# ltk-mw-rx.net
KiCad netlist of a schematic drawn in Altium Designer
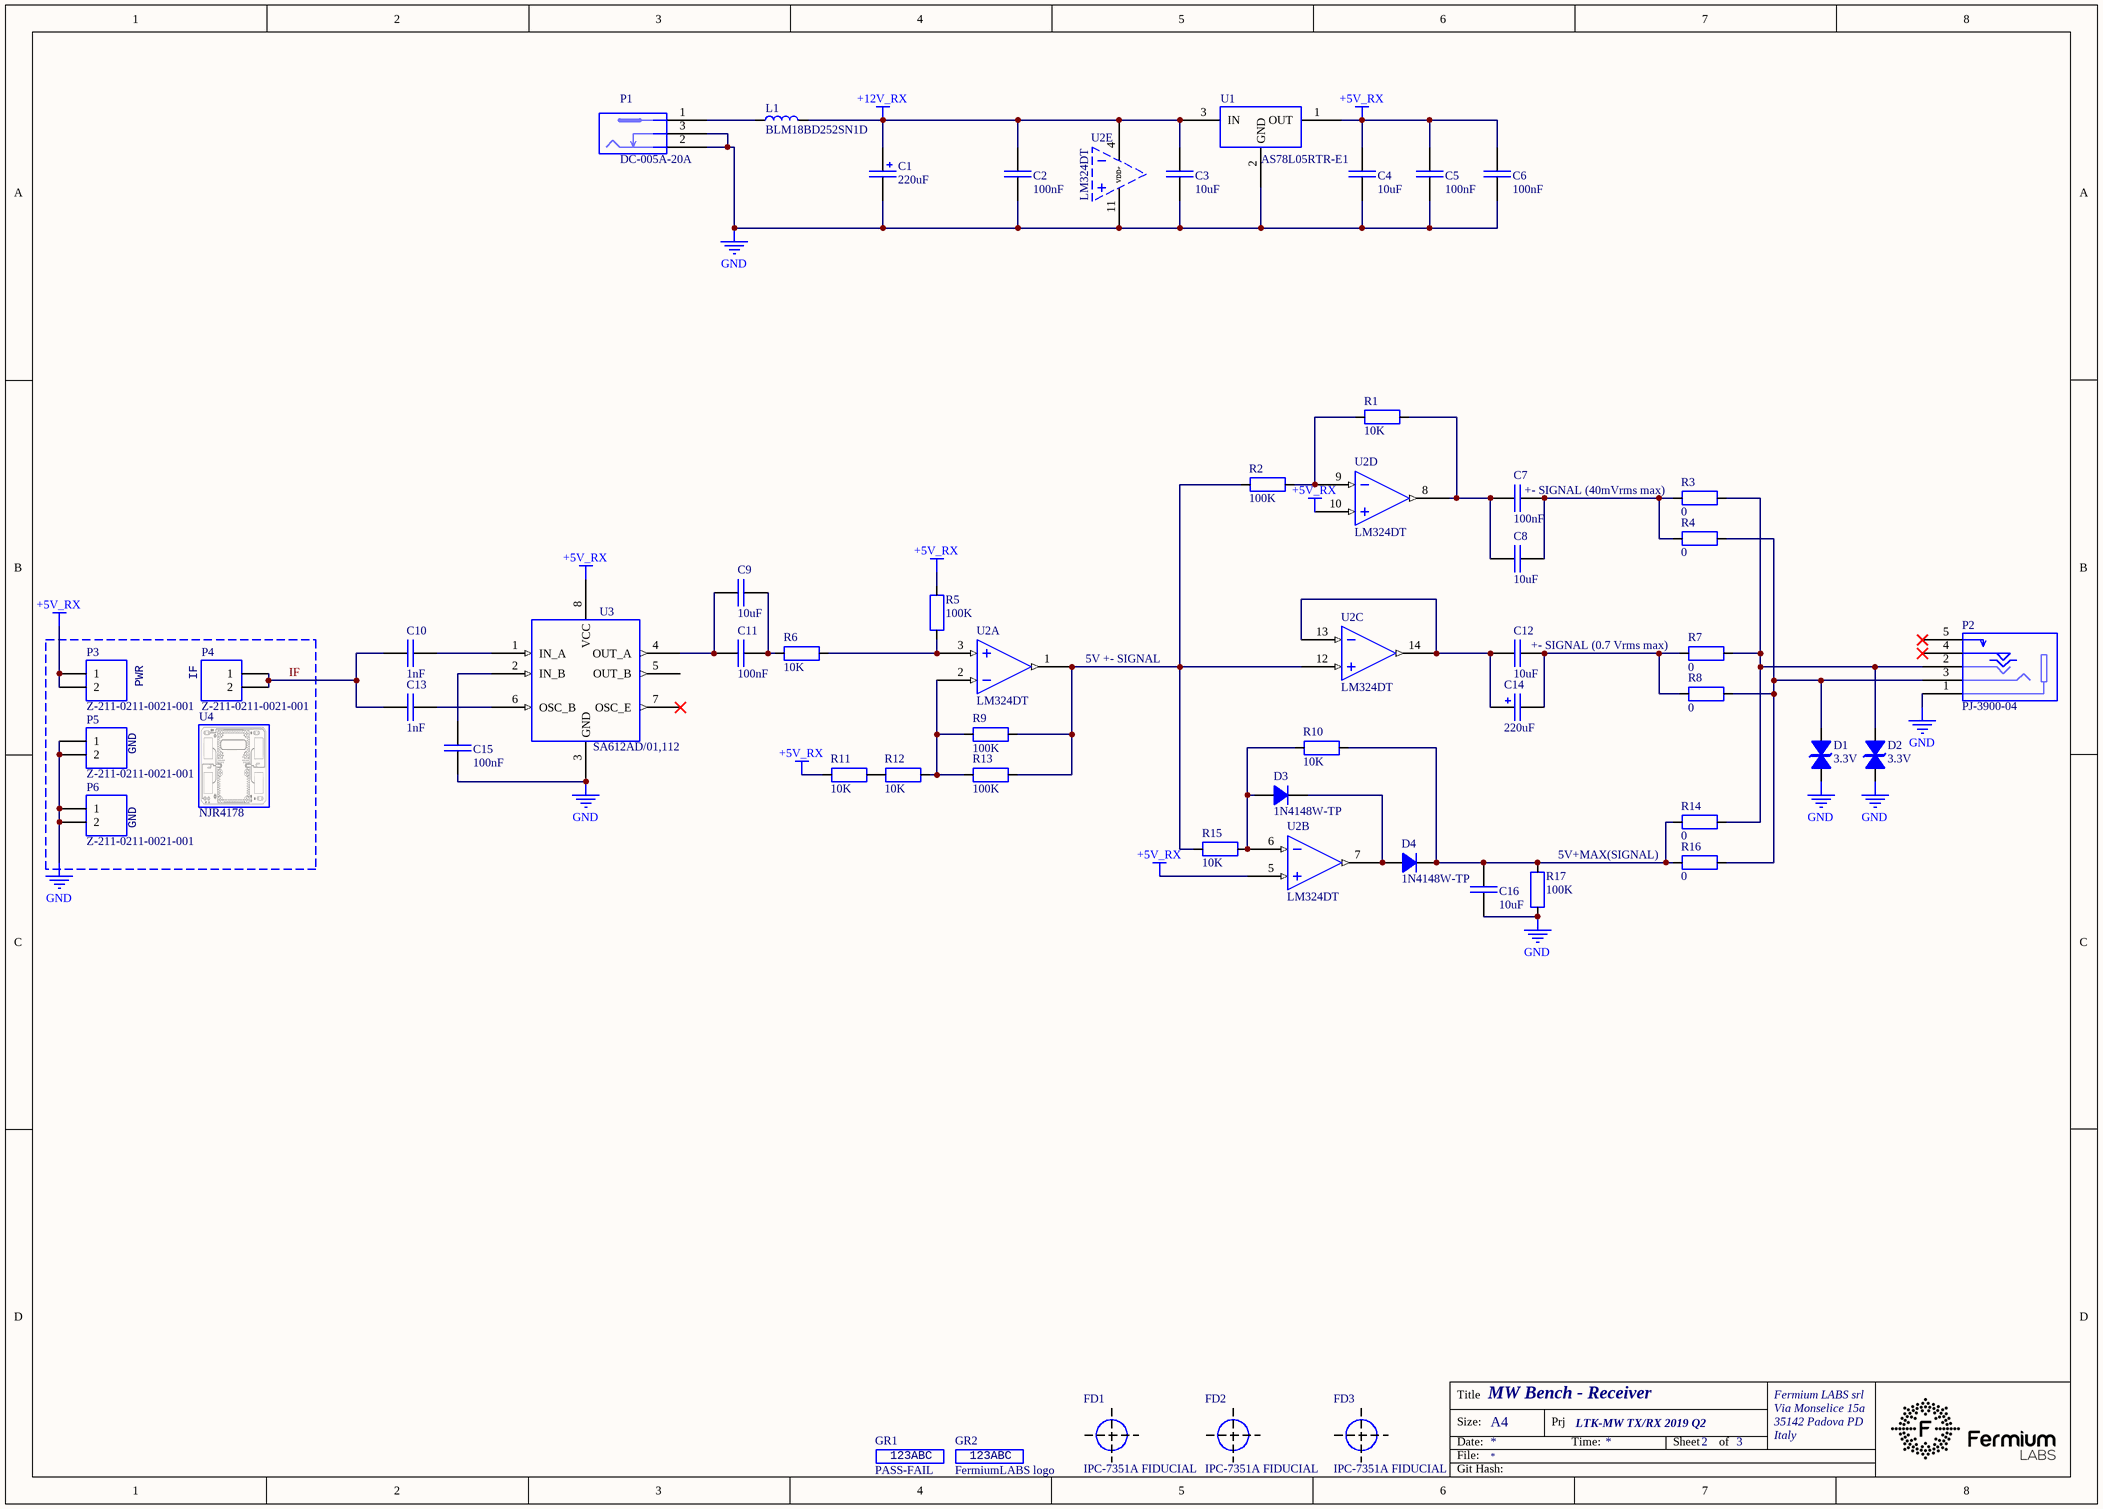
[diagram p0: ltk-mw-rx.SchDoc]

(export (version "E")
  (design (tool "Eeschema 10.0.6"))
  (components
    (comp (ref "C1")
      (value "220uF")
      (footprint "3924B366-8672-45E9-B0BE-62DACC24E783")
      (description "CAP  THT ELEC 220uF 25V 20%")
      (fields (field (name "PART NUMBER") "1a28df19-6d3e-4a71-836c-f22920f8e8ab"))
      (libsource (lib "frmdblib") (part "GENERIC_C_ELEC"))
    )
    (comp (ref "C2")
      (value "100nF")
      (footprint "CAP 0603_1608")
      (description "CAP SMD MLCC 100nF 25V 0603 X7R")
      (fields (field (name "PART NUMBER") "02841f84-ac15-41b5-9e17-915f8f067828"))
      (libsource (lib "frmdblib") (part "GENERIC_C"))
    )
    (comp (ref "C3")
      (value "10uF")
      (footprint "CAP 0805_2012")
      (description "CAP SMD MLCC 10uF 25V 0805 X5R")
      (fields (field (name "PART NUMBER") "1ffbe5a9-0884-4740-bdad-20a6a98400e6"))
      (libsource (lib "frmdblib") (part "GENERIC_C"))
    )
    (comp (ref "C4")
      (value "10uF")
      (footprint "CAP 0805_2012")
      (description "CAP SMD MLCC 10uF 25V 0805 X5R")
      (fields (field (name "PART NUMBER") "1ffbe5a9-0884-4740-bdad-20a6a98400e6"))
      (libsource (lib "frmdblib") (part "GENERIC_C"))
    )
    (comp (ref "C5")
      (value "100nF")
      (footprint "CAP 0603_1608")
      (description "CAP SMD MLCC 100nF 25V 0603 X7R")
      (fields (field (name "PART NUMBER") "02841f84-ac15-41b5-9e17-915f8f067828"))
      (libsource (lib "frmdblib") (part "GENERIC_C"))
    )
    (comp (ref "C6")
      (value "100nF")
      (footprint "CAP 0603_1608")
      (description "CAP SMD MLCC 100nF 25V 0603 X7R")
      (fields (field (name "PART NUMBER") "02841f84-ac15-41b5-9e17-915f8f067828"))
      (libsource (lib "frmdblib") (part "GENERIC_C"))
    )
    (comp (ref "C7")
      (value "100nF")
      (footprint "CAP 0603_1608")
      (description "CAP SMD MLCC 100nF 25V 0603 X7R")
      (fields (field (name "PART NUMBER") "02841f84-ac15-41b5-9e17-915f8f067828"))
      (libsource (lib "frmdblib") (part "GENERIC_C"))
    )
    (comp (ref "C8")
      (value "10uF")
      (footprint "CAP 0805_2012")
      (description "CAP SMD MLCC 10uF 25V 0805 X5R")
      (fields (field (name "PART NUMBER") "1ffbe5a9-0884-4740-bdad-20a6a98400e6"))
      (libsource (lib "frmdblib") (part "GENERIC_C"))
    )
    (comp (ref "C9")
      (value "10uF")
      (footprint "CAP 0805_2012")
      (description "CAP SMD MLCC 10uF 25V 0805 X5R")
      (fields (field (name "PART NUMBER") "1ffbe5a9-0884-4740-bdad-20a6a98400e6"))
      (libsource (lib "frmdblib") (part "GENERIC_C"))
    )
    (comp (ref "C10")
      (value "1nF")
      (footprint "CAP 0603_1608")
      (description "CAP SMD MLCC 1nF 50V 0603 X7R")
      (fields (field (name "PART NUMBER") "0eca2548-3630-4fea-a3d5-94248c1cae74"))
      (libsource (lib "frmdblib") (part "GENERIC_C"))
    )
    (comp (ref "C11")
      (value "100nF")
      (footprint "CAP 0603_1608")
      (description "CAP SMD MLCC 100nF 25V 0603 X7R")
      (fields (field (name "PART NUMBER") "02841f84-ac15-41b5-9e17-915f8f067828"))
      (libsource (lib "frmdblib") (part "GENERIC_C"))
    )
    (comp (ref "C12")
      (value "10uF")
      (footprint "CAP 0805_2012")
      (description "CAP SMD MLCC 10uF 25V 0805 X5R")
      (fields (field (name "PART NUMBER") "1ffbe5a9-0884-4740-bdad-20a6a98400e6"))
      (libsource (lib "frmdblib") (part "GENERIC_C"))
    )
    (comp (ref "C13")
      (value "1nF")
      (footprint "CAP 0603_1608")
      (description "CAP SMD MLCC 1nF 50V 0603 X7R")
      (fields (field (name "PART NUMBER") "0eca2548-3630-4fea-a3d5-94248c1cae74"))
      (libsource (lib "frmdblib") (part "GENERIC_C"))
    )
    (comp (ref "C14")
      (value "220uF")
      (footprint "3924B366-8672-45E9-B0BE-62DACC24E783")
      (description "CAP  THT ELEC 220uF 25V 20%")
      (fields (field (name "PART NUMBER") "1a28df19-6d3e-4a71-836c-f22920f8e8ab"))
      (libsource (lib "frmdblib") (part "GENERIC_C_ELEC"))
    )
    (comp (ref "C15")
      (value "100nF")
      (footprint "CAP 0603_1608")
      (description "CAP SMD MLCC 100nF 25V 0603 X7R")
      (fields (field (name "PART NUMBER") "02841f84-ac15-41b5-9e17-915f8f067828"))
      (libsource (lib "frmdblib") (part "GENERIC_C"))
    )
    (comp (ref "C16")
      (value "10uF")
      (footprint "CAP 0805_2012")
      (description "CAP SMD MLCC 10uF 25V 0805 X5R")
      (fields (field (name "PART NUMBER") "1ffbe5a9-0884-4740-bdad-20a6a98400e6"))
      (libsource (lib "frmdblib") (part "GENERIC_C"))
    )
    (comp (ref "D1")
      (value "3.3V")
      (footprint "SOD523F")
      (description "DIODE SMD TVS 3.3V BIDIRECTIONAL SOD-523")
      (fields (field (name "PART NUMBER") "d6266fd0-7428-4fb9-a062-338cdce926fd"))
      (libsource (lib "frmdblib") (part "GENERIC_D_TVS_BI"))
    )
    (comp (ref "D2")
      (value "3.3V")
      (footprint "SOD523F")
      (description "DIODE SMD TVS 3.3V BIDIRECTIONAL SOD-523")
      (fields (field (name "PART NUMBER") "d6266fd0-7428-4fb9-a062-338cdce926fd"))
      (libsource (lib "frmdblib") (part "GENERIC_D_TVS_BI"))
    )
    (comp (ref "D3")
      (value "1N4148W-TP")
      (footprint "SOD-123")
      (description "DIODE SMD 100V 150mA 1.5Vf SOD-123 4148")
      (fields (field (name "PART NUMBER") "5e920700-75df-48e3-84dd-8f9f777caed8"))
      (libsource (lib "frmdblib") (part "GENERIC_D"))
    )
    (comp (ref "D4")
      (value "1N4148W-TP")
      (footprint "SOD-123")
      (description "DIODE SMD 100V 150mA 1.5Vf SOD-123 4148")
      (fields (field (name "PART NUMBER") "5e920700-75df-48e3-84dd-8f9f777caed8"))
      (libsource (lib "frmdblib") (part "GENERIC_D"))
    )
    (comp (ref "FD1")
      (value "IPC-7351A FIDUCIAL")
      (footprint "FIDUCIAL-IPC-7351A")
      (description "GRAPHICS FIDUCIAL IPC-7351A")
      (fields (field (name "PART NUMBER") "19da4612-eb95-43bb-9984-553a52b2a224"))
      (libsource (lib "frmdblib") (part "GENERIC_FIDUCIAL"))
    )
    (comp (ref "FD2")
      (value "IPC-7351A FIDUCIAL")
      (footprint "FIDUCIAL-IPC-7351A")
      (description "GRAPHICS FIDUCIAL IPC-7351A")
      (fields (field (name "PART NUMBER") "19da4612-eb95-43bb-9984-553a52b2a224"))
      (libsource (lib "frmdblib") (part "GENERIC_FIDUCIAL"))
    )
    (comp (ref "FD3")
      (value "IPC-7351A FIDUCIAL")
      (footprint "FIDUCIAL-IPC-7351A")
      (description "GRAPHICS FIDUCIAL IPC-7351A")
      (fields (field (name "PART NUMBER") "19da4612-eb95-43bb-9984-553a52b2a224"))
      (libsource (lib "frmdblib") (part "GENERIC_FIDUCIAL"))
    )
    (comp (ref "GR1")
      (value "PASS-FAIL")
      (footprint "0B1556B7-A534-4801-B57D-01EFA34B1205")
      (description "GRAPHICS PASS-FAIL MARK")
      (fields (field (name "PART NUMBER") "d1abe19f-3fed-4f20-b2ed-afc0ffbc6628"))
      (libsource (lib "frmdblib") (part "GENERIC_GRAPHIC"))
    )
    (comp (ref "GR2")
      (value "FermiumLABS logo")
      (footprint "5394DE47-A0E8-4329-8464-7791B7C19310")
      (description "GRAPHICS LOGO FERMIUM LABS SRL")
      (fields (field (name "PART NUMBER") "50f8ea88-0034-49fe-a263-d8e97bc35e2f"))
      (libsource (lib "frmdblib") (part "GENERIC_GRAPHIC"))
    )
    (comp (ref "L1")
      (value "BLM18BD252SN1D")
      (footprint "FER 0603_1608")
      (description "FER SMD CHIP 0603 400mA 1k@100MHz 500mOhm")
      (fields (field (name "PART NUMBER") "c9e30ae8-9d5b-4135-a079-b1147da846d8"))
      (libsource (lib "frmdblib") (part "GENERIC_L"))
    )
    (comp (ref "P1")
      (value "DC-005A-20A")
      (footprint "F0972D8A-C5C0-4A84-836D-A9666EE65C2D")
      (description "CONN THT DC JACK 0.5A 30VDC 5Kcycles")
      (fields (field (name "PART NUMBER") "b53db51a-1725-412b-9039-fa7a45c7c438"))
      (libsource (lib "frmdblib") (part "34A1CD0B-E262-46EF-B9F1-39CB809C308F"))
    )
    (comp (ref "P2")
      (value "PJ-3900-04")
      (footprint "7EF2B92C-0FC9-4C85-B662-5CEC65BFCCC4")
      (description "CONN THT 3.5mm AUDIO STEREO AUX SWITCH")
      (fields (field (name "PART NUMBER") "80507a24-5d7c-4cf5-953e-f54832d54564"))
      (libsource (lib "frmdblib") (part "46E41D2F-79BD-46AC-B778-70B2D50A946A"))
    )
    (comp (ref "P3")
      (value "Z-211-0211-0021-001")
      (footprint "0FBEB40D-2B6D-43C7-945F-A2D40A82B953")
      (description "CONN THT PIN HEADER 2P MALE 2.54mm")
      (fields (field (name "PART NUMBER") "fb9043ef-1dd5-4a9c-8c1a-da0c667690ac"))
      (libsource (lib "frmdblib") (part "Header 2"))
    )
    (comp (ref "P4")
      (value "Z-211-0211-0021-001")
      (footprint "0FBEB40D-2B6D-43C7-945F-A2D40A82B953")
      (description "CONN THT PIN HEADER 2P MALE 2.54mm")
      (fields (field (name "PART NUMBER") "fb9043ef-1dd5-4a9c-8c1a-da0c667690ac"))
      (libsource (lib "") (part "Header 2_1"))
    )
    (comp (ref "P5")
      (value "Z-211-0211-0021-001")
      (footprint "0FBEB40D-2B6D-43C7-945F-A2D40A82B953")
      (description "CONN THT PIN HEADER 2P MALE 2.54mm")
      (fields (field (name "PART NUMBER") "fb9043ef-1dd5-4a9c-8c1a-da0c667690ac"))
      (libsource (lib "frmdblib") (part "Header 2"))
    )
    (comp (ref "P6")
      (value "Z-211-0211-0021-001")
      (footprint "0FBEB40D-2B6D-43C7-945F-A2D40A82B953")
      (description "CONN THT PIN HEADER 2P MALE 2.54mm")
      (fields (field (name "PART NUMBER") "fb9043ef-1dd5-4a9c-8c1a-da0c667690ac"))
      (libsource (lib "frmdblib") (part "Header 2"))
    )
    (comp (ref "R1")
      (value "10K")
      (footprint "RES 0603_1608")
      (description "RES SMD 10K OHM 1% 1/10W 0603")
      (fields (field (name "PART NUMBER") "93242766-ba1d-462d-b58f-ce1dfc4129c8"))
      (libsource (lib "frmdblib") (part "GENERIC_R"))
    )
    (comp (ref "R2")
      (value "100K")
      (footprint "RES 0603_1608")
      (description "RES SMD 100K OHM 1% 1/10W 0603")
      (fields (field (name "PART NUMBER") "76af10b3-9d85-4b5c-a2d6-26cc74f432f7"))
      (libsource (lib "frmdblib") (part "GENERIC_R"))
    )
    (comp (ref "R3")
      (value "0")
      (footprint "RES 0603_1608")
      (description "RES SMD 0 OHM 5% 1/10W 0603")
      (fields (field (name "PART NUMBER") "6ae227f9-847f-4766-8522-e11a83531204"))
      (libsource (lib "frmdblib") (part "GENERIC_R"))
    )
    (comp (ref "R4")
      (value "0")
      (footprint "RES 0603_1608")
      (description "RES SMD 0 OHM 5% 1/10W 0603")
      (fields (field (name "PART NUMBER") "6ae227f9-847f-4766-8522-e11a83531204"))
      (libsource (lib "frmdblib") (part "GENERIC_R"))
    )
    (comp (ref "R5")
      (value "100K")
      (footprint "RES 0603_1608")
      (description "RES SMD 100K OHM 1% 1/10W 0603")
      (fields (field (name "PART NUMBER") "76af10b3-9d85-4b5c-a2d6-26cc74f432f7"))
      (libsource (lib "frmdblib") (part "GENERIC_R"))
    )
    (comp (ref "R6")
      (value "10K")
      (footprint "RES 0603_1608")
      (description "RES SMD 10K OHM 1% 1/10W 0603")
      (fields (field (name "PART NUMBER") "93242766-ba1d-462d-b58f-ce1dfc4129c8"))
      (libsource (lib "frmdblib") (part "GENERIC_R"))
    )
    (comp (ref "R7")
      (value "0")
      (footprint "RES 0603_1608")
      (description "RES SMD 0 OHM 5% 1/10W 0603")
      (fields (field (name "PART NUMBER") "6ae227f9-847f-4766-8522-e11a83531204"))
      (libsource (lib "frmdblib") (part "GENERIC_R"))
    )
    (comp (ref "R8")
      (value "0")
      (footprint "RES 0603_1608")
      (description "RES SMD 0 OHM 5% 1/10W 0603")
      (fields (field (name "PART NUMBER") "6ae227f9-847f-4766-8522-e11a83531204"))
      (libsource (lib "frmdblib") (part "GENERIC_R"))
    )
    (comp (ref "R9")
      (value "100K")
      (footprint "RES 0603_1608")
      (description "RES SMD 100K OHM 1% 1/10W 0603")
      (fields (field (name "PART NUMBER") "76af10b3-9d85-4b5c-a2d6-26cc74f432f7"))
      (libsource (lib "frmdblib") (part "GENERIC_R"))
    )
    (comp (ref "R10")
      (value "10K")
      (footprint "RES 0603_1608")
      (description "RES SMD 10K OHM 1% 1/10W 0603")
      (fields (field (name "PART NUMBER") "93242766-ba1d-462d-b58f-ce1dfc4129c8"))
      (libsource (lib "frmdblib") (part "GENERIC_R"))
    )
    (comp (ref "R11")
      (value "10K")
      (footprint "RES 0603_1608")
      (description "RES SMD 10K OHM 1% 1/10W 0603")
      (fields (field (name "PART NUMBER") "93242766-ba1d-462d-b58f-ce1dfc4129c8"))
      (libsource (lib "frmdblib") (part "GENERIC_R"))
    )
    (comp (ref "R12")
      (value "10K")
      (footprint "RES 0603_1608")
      (description "RES SMD 10K OHM 1% 1/10W 0603")
      (fields (field (name "PART NUMBER") "93242766-ba1d-462d-b58f-ce1dfc4129c8"))
      (libsource (lib "frmdblib") (part "GENERIC_R"))
    )
    (comp (ref "R13")
      (value "100K")
      (footprint "RES 0603_1608")
      (description "RES SMD 100K OHM 1% 1/10W 0603")
      (fields (field (name "PART NUMBER") "76af10b3-9d85-4b5c-a2d6-26cc74f432f7"))
      (libsource (lib "frmdblib") (part "GENERIC_R"))
    )
    (comp (ref "R14")
      (value "0")
      (footprint "RES 0603_1608")
      (description "RES SMD 0 OHM 5% 1/10W 0603")
      (fields (field (name "PART NUMBER") "6ae227f9-847f-4766-8522-e11a83531204"))
      (libsource (lib "frmdblib") (part "GENERIC_R"))
    )
    (comp (ref "R15")
      (value "10K")
      (footprint "RES 0603_1608")
      (description "RES SMD 10K OHM 1% 1/10W 0603")
      (fields (field (name "PART NUMBER") "93242766-ba1d-462d-b58f-ce1dfc4129c8"))
      (libsource (lib "frmdblib") (part "GENERIC_R"))
    )
    (comp (ref "R16")
      (value "0")
      (footprint "RES 0603_1608")
      (description "RES SMD 0 OHM 5% 1/10W 0603")
      (fields (field (name "PART NUMBER") "6ae227f9-847f-4766-8522-e11a83531204"))
      (libsource (lib "frmdblib") (part "GENERIC_R"))
    )
    (comp (ref "R17")
      (value "100K")
      (footprint "RES 0603_1608")
      (description "RES SMD 100K OHM 1% 1/10W 0603")
      (fields (field (name "PART NUMBER") "76af10b3-9d85-4b5c-a2d6-26cc74f432f7"))
      (libsource (lib "frmdblib") (part "GENERIC_R"))
    )
    (comp (ref "U1")
      (value "AS78L05RTR-E1")
      (footprint "E733EFB9-FE91-4AE9-9197-29251971C3DC")
      (description "IC SMD LINEAR VOLTAGE REGULATOR 5V 100mA SOT-89")
      (fields (field (name "PART NUMBER") "fd64863e-487f-4688-b264-696c0ba5456b"))
      (libsource (lib "frmdblib") (part "FCB39772-D6AF-4D61-BC58-A46A50428B6B"))
    )
    (comp (ref "U2")
      (value "LM324DT")
      (footprint "34355DA5-B1DA-47C2-A88A-ECF82120A4F7")
      (description "IC SMD OPAMP LM324DT SO-14")
      (fields (field (name "PART NUMBER") "21a85167-c328-42f7-a52e-365842c6dad3"))
      (libsource (lib "frmdblib") (part "B8DB4B19-8E9C-4F46-A390-7A352E041443"))
    )
    (comp (ref "U3")
      (value "SA612AD/01,112")
      (footprint "TI SOIC-8 D")
      (description "IC SMD RF MIXER SA612A SOIC-8")
      (fields (field (name "PART NUMBER") "a9622f6c-68f2-4f08-abc9-76f38977fdd3"))
      (libsource (lib "frmdblib") (part "A45114BD-821B-4F2C-91DA-34880533DC1E"))
    )
    (comp (ref "U4")
      (value "NJR4178")
      (footprint "25B19271-CD6F-4BC8-A99B-F617D566DC9C")
      (description "MODULE THT RADAR DOPPLER 10.525GHz NJR4178")
      (fields (field (name "PART NUMBER") "f0e19a38-18de-4253-8da2-aebb0c4083bd"))
      (libsource (lib "frmdblib") (part "687D5558-C857-4646-9F75-B643D2B4D9DF"))
    )
  )
  (nets
    (net (code "1") (name "+5V_RX") (class "Default")
      (node (ref "C4") (pin "2") (pintype "passive"))
      (node (ref "C5") (pin "2") (pintype "passive"))
      (node (ref "C6") (pin "2") (pintype "passive"))
      (node (ref "P3") (pin "1") (pinfunction "1_1") (pintype "passive"))
      (node (ref "P3") (pin "2") (pinfunction "2_2") (pintype "passive"))
      (node (ref "R11") (pin "2") (pintype "passive"))
      (node (ref "R5") (pin "1") (pintype "passive"))
      (node (ref "U1") (pin "1") (pinfunction "OUT_1") (pintype "passive"))
      (node (ref "U2") (pin "10") (pinfunction "IN+_10") (pintype "input"))
      (node (ref "U2") (pin "5") (pinfunction "IN+_5") (pintype "input"))
      (node (ref "U3") (pin "8") (pinfunction "VCC_8") (pintype "power_in"))
    )
    (net (code "2") (name "+12V_RX") (class "Default")
      (node (ref "C1") (pin "1") (pintype "passive"))
      (node (ref "C2") (pin "2") (pintype "passive"))
      (node (ref "C3") (pin "2") (pintype "passive"))
      (node (ref "L1") (pin "2") (pintype "passive"))
      (node (ref "U1") (pin "3") (pinfunction "IN_3") (pintype "passive"))
      (node (ref "U2") (pin "4") (pinfunction "VDD+_4") (pintype "power_in"))
    )
    (net (code "3") (name "/IF") (class "Default")
      (node (ref "C10") (pin "1") (pintype "passive"))
      (node (ref "C13") (pin "1") (pintype "passive"))
      (node (ref "P4") (pin "1") (pinfunction "1_1") (pintype "passive"))
      (node (ref "P4") (pin "2") (pinfunction "2_2") (pintype "passive"))
    )
    (net (code "4") (name "GND") (class "Default")
      (node (ref "C1") (pin "2") (pintype "passive"))
      (node (ref "C15") (pin "2") (pintype "passive"))
      (node (ref "C16") (pin "2") (pintype "passive"))
      (node (ref "C2") (pin "1") (pintype "passive"))
      (node (ref "C3") (pin "1") (pintype "passive"))
      (node (ref "C4") (pin "1") (pintype "passive"))
      (node (ref "C5") (pin "1") (pintype "passive"))
      (node (ref "C6") (pin "1") (pintype "passive"))
      (node (ref "D1") (pin "2") (pintype "passive"))
      (node (ref "D2") (pin "2") (pintype "passive"))
      (node (ref "P1") (pin "2") (pinfunction "2_2") (pintype "passive"))
      (node (ref "P1") (pin "3") (pinfunction "3_3") (pintype "passive"))
      (node (ref "P2") (pin "1") (pinfunction "GND_1") (pintype "passive"))
      (node (ref "P5") (pin "1") (pinfunction "1_1") (pintype "passive"))
      (node (ref "P5") (pin "2") (pinfunction "2_2") (pintype "passive"))
      (node (ref "P6") (pin "1") (pinfunction "1_1") (pintype "passive"))
      (node (ref "P6") (pin "2") (pinfunction "2_2") (pintype "passive"))
      (node (ref "R17") (pin "1") (pintype "passive"))
      (node (ref "U1") (pin "2") (pinfunction "GND_2") (pintype "passive"))
      (node (ref "U2") (pin "11") (pinfunction "VDD-_11") (pintype "power_in"))
      (node (ref "U3") (pin "3") (pinfunction "GND_3") (pintype "power_in"))
    )
    (net (code "5") (name "Net-(C7-Pad2)") (class "Default")
      (node (ref "C7") (pin "2") (pintype "passive"))
      (node (ref "C8") (pin "2") (pintype "passive"))
      (node (ref "R3") (pin "2") (pintype "passive"))
      (node (ref "R4") (pin "2") (pintype "passive"))
    )
    (net (code "6") (name "Net-(C11-Pad2)") (class "Default")
      (node (ref "C11") (pin "2") (pintype "passive"))
      (node (ref "C9") (pin "2") (pintype "passive"))
      (node (ref "R6") (pin "2") (pintype "passive"))
    )
    (net (code "7") (name "Net-(C12-Pad1)") (class "Default")
      (node (ref "C12") (pin "1") (pintype "passive"))
      (node (ref "C14") (pin "2") (pintype "passive"))
      (node (ref "R7") (pin "2") (pintype "passive"))
      (node (ref "R8") (pin "2") (pintype "passive"))
    )
    (net (code "8") (name "Net-(D3-A)") (class "Default")
      (node (ref "D3") (pin "2") (pinfunction "A_2") (pintype "passive"))
      (node (ref "R10") (pin "2") (pintype "passive"))
      (node (ref "R15") (pin "1") (pintype "passive"))
      (node (ref "U2") (pin "6") (pinfunction "IN-_6") (pintype "input"))
    )
    (net (code "9") (name "Net-(D3-K)") (class "Default")
      (node (ref "D3") (pin "1") (pinfunction "K_1") (pintype "passive"))
      (node (ref "D4") (pin "2") (pinfunction "A_2") (pintype "passive"))
      (node (ref "U2") (pin "7") (pinfunction "OUT_7") (pintype "output"))
    )
    (net (code "10") (name "Net-(D4-K)") (class "Default")
      (node (ref "C16") (pin "1") (pintype "passive"))
      (node (ref "D4") (pin "1") (pinfunction "K_1") (pintype "passive"))
      (node (ref "R10") (pin "1") (pintype "passive"))
      (node (ref "R14") (pin "2") (pintype "passive"))
      (node (ref "R16") (pin "2") (pintype "passive"))
      (node (ref "R17") (pin "2") (pintype "passive"))
    )
    (net (code "11") (name "Net-(L1-Pad1)") (class "Default")
      (node (ref "L1") (pin "1") (pintype "passive"))
      (node (ref "P1") (pin "1") (pinfunction "1_1") (pintype "passive"))
    )
    (net (code "12") (name "Net-(P2-L)") (class "Default")
      (node (ref "D1") (pin "1") (pintype "passive"))
      (node (ref "P2") (pin "3") (pinfunction "L_3") (pintype "passive"))
      (node (ref "R16") (pin "1") (pintype "passive"))
      (node (ref "R4") (pin "1") (pintype "passive"))
      (node (ref "R8") (pin "1") (pintype "passive"))
    )
    (net (code "13") (name "Net-(P2-R)") (class "Default")
      (node (ref "D2") (pin "1") (pintype "passive"))
      (node (ref "P2") (pin "2") (pinfunction "R_2") (pintype "passive"))
      (node (ref "R14") (pin "1") (pintype "passive"))
      (node (ref "R3") (pin "1") (pintype "passive"))
      (node (ref "R7") (pin "1") (pintype "passive"))
    )
    (net (code "14") (name "Net-(R11-Pad1)") (class "Default")
      (node (ref "R11") (pin "1") (pintype "passive"))
      (node (ref "R12") (pin "2") (pintype "passive"))
    )
    (net (code "15") (name "Net-(U2A-IN+)") (class "Default")
      (node (ref "R5") (pin "2") (pintype "passive"))
      (node (ref "R6") (pin "1") (pintype "passive"))
      (node (ref "U2") (pin "3") (pinfunction "IN+_3") (pintype "input"))
    )
    (net (code "16") (name "Net-(U2A-IN-)") (class "Default")
      (node (ref "R12") (pin "1") (pintype "passive"))
      (node (ref "R13") (pin "2") (pintype "passive"))
      (node (ref "R9") (pin "2") (pintype "passive"))
      (node (ref "U2") (pin "2") (pinfunction "IN-_2") (pintype "input"))
    )
    (net (code "17") (name "Net-(U2A-OUT)") (class "Default")
      (node (ref "R13") (pin "1") (pintype "passive"))
      (node (ref "R15") (pin "2") (pintype "passive"))
      (node (ref "R2") (pin "2") (pintype "passive"))
      (node (ref "R9") (pin "1") (pintype "passive"))
      (node (ref "U2") (pin "1") (pinfunction "OUT_1") (pintype "output"))
      (node (ref "U2") (pin "12") (pinfunction "IN+_12") (pintype "input"))
    )
    (net (code "18") (name "Net-(U2C-IN-)") (class "Default")
      (node (ref "C12") (pin "2") (pintype "passive"))
      (node (ref "C14") (pin "1") (pintype "passive"))
      (node (ref "U2") (pin "13") (pinfunction "IN-_13") (pintype "input"))
      (node (ref "U2") (pin "14") (pinfunction "OUT_14") (pintype "output"))
    )
    (net (code "19") (name "Net-(U2D-IN-)") (class "Default")
      (node (ref "R1") (pin "2") (pintype "passive"))
      (node (ref "R2") (pin "1") (pintype "passive"))
      (node (ref "U2") (pin "9") (pinfunction "IN-_9") (pintype "input"))
    )
    (net (code "20") (name "Net-(U2D-OUT)") (class "Default")
      (node (ref "C7") (pin "1") (pintype "passive"))
      (node (ref "C8") (pin "1") (pintype "passive"))
      (node (ref "R1") (pin "1") (pintype "passive"))
      (node (ref "U2") (pin "8") (pinfunction "OUT_8") (pintype "output"))
    )
    (net (code "21") (name "Net-(U3-IN_A)") (class "Default")
      (node (ref "C10") (pin "2") (pintype "passive"))
      (node (ref "U3") (pin "1") (pinfunction "IN_A_1") (pintype "input"))
    )
    (net (code "22") (name "Net-(U3-IN_B)") (class "Default")
      (node (ref "C15") (pin "1") (pintype "passive"))
      (node (ref "U3") (pin "2") (pinfunction "IN_B_2") (pintype "input"))
    )
    (net (code "23") (name "Net-(U3-OSC_B)") (class "Default")
      (node (ref "C13") (pin "2") (pintype "passive"))
      (node (ref "U3") (pin "6") (pinfunction "OSC_B_6") (pintype "input"))
    )
    (net (code "24") (name "Net-(U3-OUT_A)") (class "Default")
      (node (ref "C11") (pin "1") (pintype "passive"))
      (node (ref "C9") (pin "1") (pintype "passive"))
      (node (ref "U3") (pin "4") (pinfunction "OUT_A_4") (pintype "output"))
    )
    (net (code "25") (name "unconnected-(P2-AUX-Pad4)") (class "Default")
      (node (ref "P2") (pin "4") (pinfunction "AUX_4") (pintype "passive+no_connect"))
    )
    (net (code "26") (name "unconnected-(P2-AUX-Pad5)") (class "Default")
      (node (ref "P2") (pin "5") (pinfunction "AUX_5") (pintype "passive+no_connect"))
    )
    (net (code "27") (name "unconnected-(U3-OSC_E-Pad7)") (class "Default")
      (node (ref "U3") (pin "7") (pinfunction "OSC_E_7") (pintype "output+no_connect"))
    )
    (net (code "28") (name "unconnected-(U3-OUT_B-Pad5)") (class "Default")
      (node (ref "U3") (pin "5") (pinfunction "OUT_B_5") (pintype "output"))
    )
  )
)
